# MgdOpna.net
KiCad netlist of a schematic drawn in EAGLE
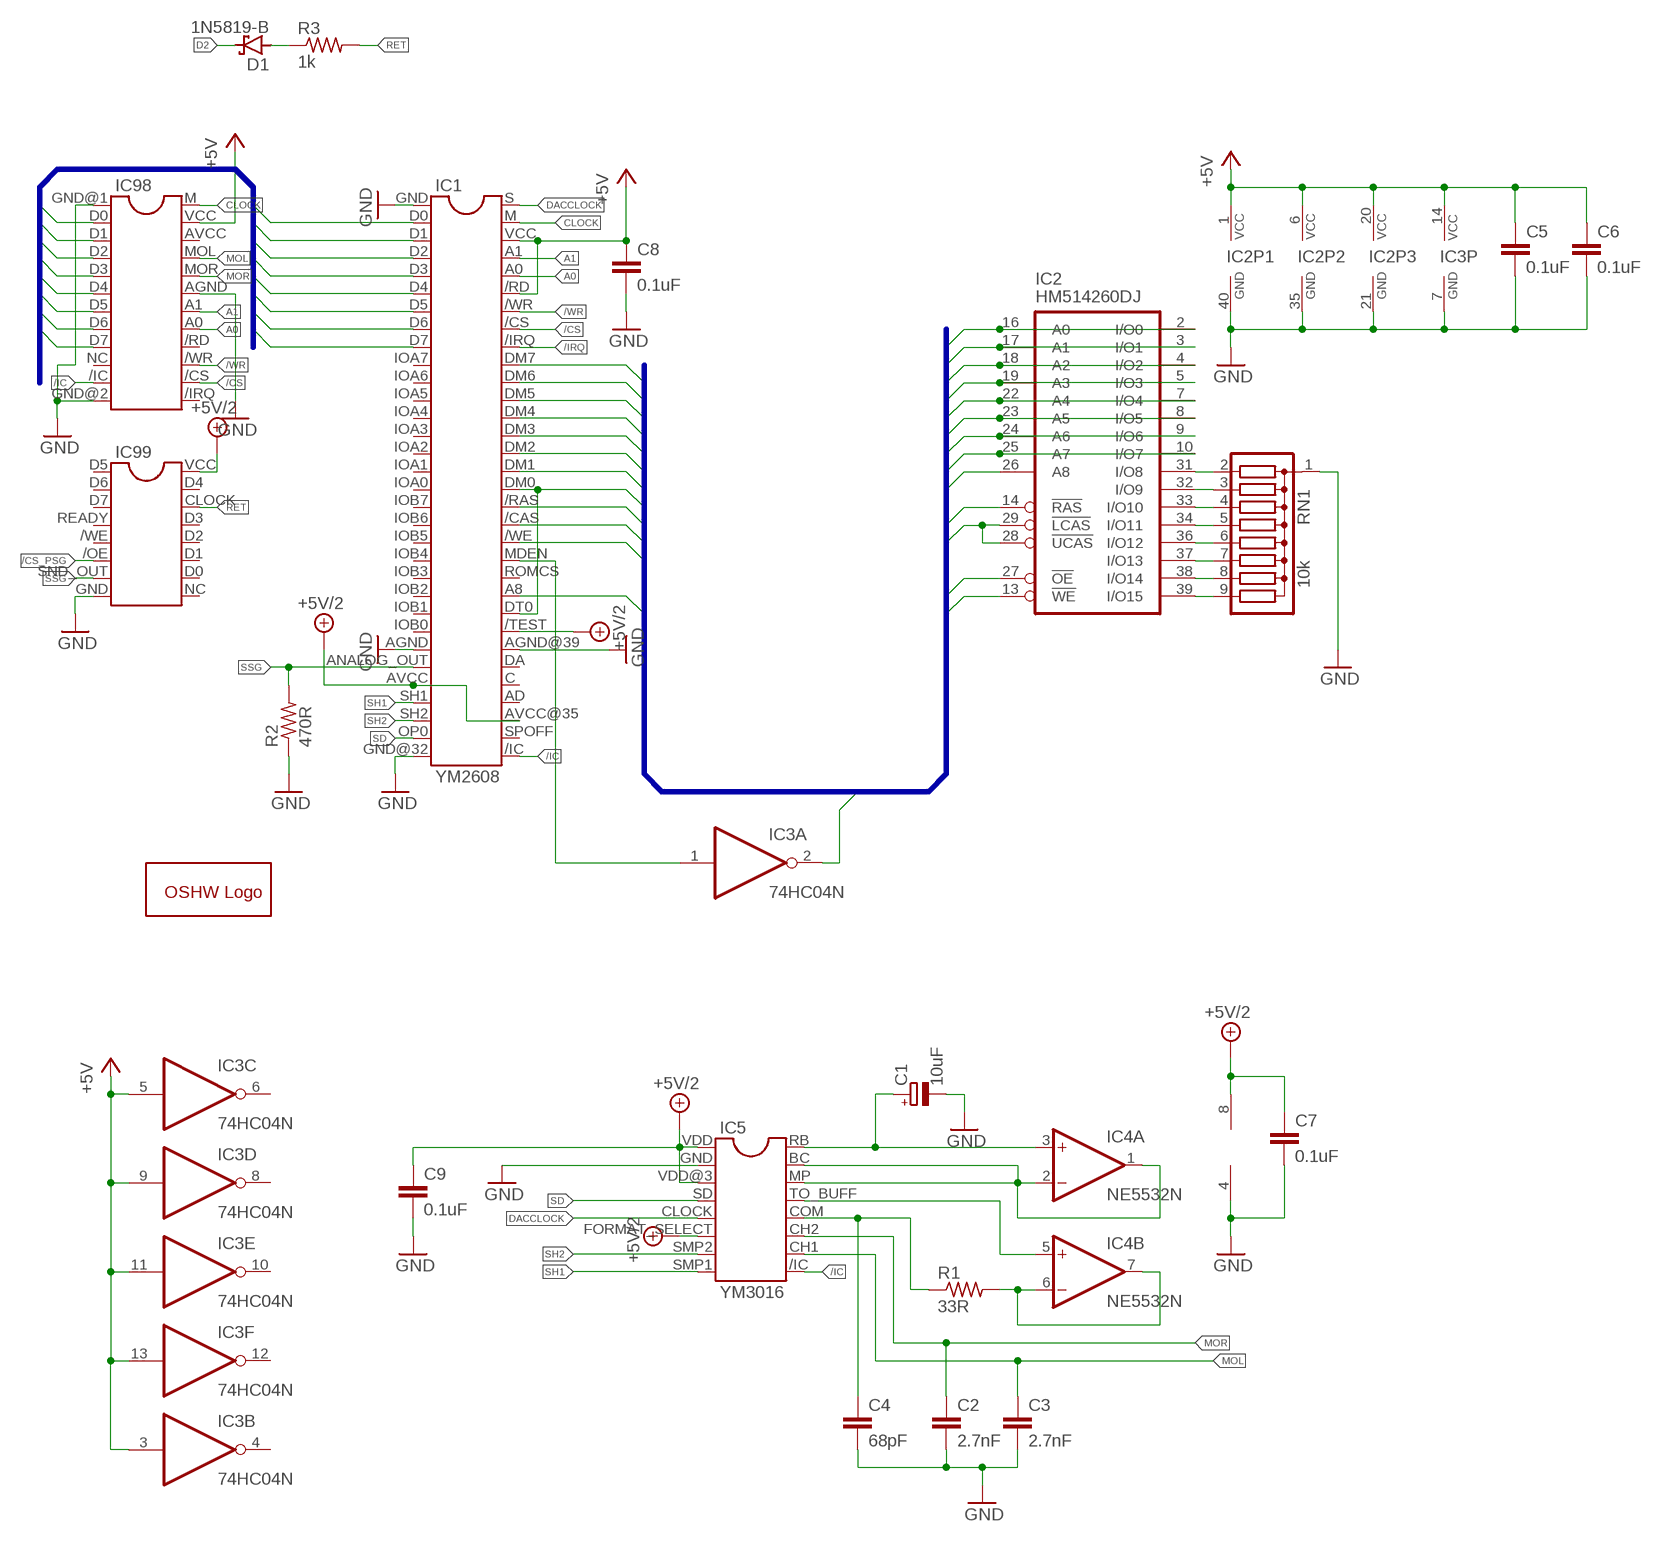
[diagram p0: schematic, sheet 1]

(export (version "E")
  (design (tool "Eeschema 10.0.6"))
  (components
    (comp (ref "C1")
      (value "10uF")
      (footprint "eagle-import:E2,5-5")
      (libsource (lib "eagle-import") (part "CPOL-EUE2.5-5"))
    )
    (comp (ref "C2")
      (value "2.7nF")
      (footprint "eagle-import:C025-024X044")
      (libsource (lib "eagle-import") (part "C-EU025-024X044"))
    )
    (comp (ref "C3")
      (value "2.7nF")
      (footprint "eagle-import:C025-024X044")
      (libsource (lib "eagle-import") (part "C-EU025-024X044"))
    )
    (comp (ref "C4")
      (value "68pF")
      (footprint "eagle-import:C025-024X044")
      (libsource (lib "eagle-import") (part "C-EU025-024X044"))
    )
    (comp (ref "C5")
      (value "0.1uF")
      (footprint "eagle-import:C025-024X044")
      (libsource (lib "eagle-import") (part "C-EU025-024X044"))
    )
    (comp (ref "C6")
      (value "0.1uF")
      (footprint "eagle-import:C025-024X044")
      (libsource (lib "eagle-import") (part "C-EU025-024X044"))
    )
    (comp (ref "C7")
      (value "0.1uF")
      (footprint "eagle-import:C025-024X044")
      (libsource (lib "eagle-import") (part "C-EU025-024X044"))
    )
    (comp (ref "C8")
      (value "0.1uF")
      (footprint "eagle-import:C025-024X044")
      (libsource (lib "eagle-import") (part "C-EU025-024X044"))
    )
    (comp (ref "C9")
      (value "0.1uF")
      (footprint "eagle-import:C025-024X044")
      (libsource (lib "eagle-import") (part "C-EU025-024X044"))
    )
    (comp (ref "D1")
      (value "1N5819-B")
      (footprint "eagle-import:DO41-7.6")
      (libsource (lib "eagle-import") (part "1N5819-B"))
    )
    (comp (ref "GOLD_ORB_SM1")
      (value "OSHWLOGOLOGO8MM")
      (footprint "eagle-import:OSHW_8MM")
      (libsource (lib "eagle-import") (part "OSHWLOGOLOGO8MM"))
    )
    (comp (ref "IC1")
      (value "YM2608")
      (footprint "eagle-import:YM2608")
      (libsource (lib "eagle-import") (part "YM2608"))
    )
    (comp (ref "IC2")
      (value "HM514260DJ")
      (footprint "eagle-import:SOJ40-4")
      (libsource (lib "eagle-import") (part "HM514260DJ"))
    )
    (comp (ref "IC3")
      (value "74HC04N")
      (footprint "eagle-import:DIL14")
      (libsource (lib "eagle-import") (part "7404NHC"))
    )
    (comp (ref "IC4")
      (value "NE5532N")
      (footprint "eagle-import:DIL08")
      (libsource (lib "eagle-import") (part "NE5532N"))
    )
    (comp (ref "IC5")
      (value "YM3016")
      (footprint "eagle-import:YM3016")
      (libsource (lib "eagle-import") (part "YM3016"))
    )
    (comp (ref "IC98")
      (value "YM2612YM2612_NOSILK")
      (footprint "eagle-import:YM2612_NOSILK")
      (libsource (lib "eagle-import") (part "YM2612YM2612_NOSILK"))
    )
    (comp (ref "IC99")
      (value "SN76489SN76489_NOSILK")
      (footprint "eagle-import:SN76489_NOSILK")
      (libsource (lib "eagle-import") (part "SN76489SN76489_NOSILK"))
    )
    (comp (ref "R1")
      (value "33R")
      (footprint "eagle-import:0204_7")
      (libsource (lib "eagle-import") (part "R-US_0204/7"))
    )
    (comp (ref "R2")
      (value "470R")
      (footprint "eagle-import:0204_7")
      (libsource (lib "eagle-import") (part "R-US_0204/7"))
    )
    (comp (ref "R3")
      (value "1k")
      (footprint "eagle-import:0204_7")
      (libsource (lib "eagle-import") (part "R-US_0204/7"))
    )
    (comp (ref "RN1")
      (value "10k")
      (footprint "eagle-import:SIL9")
      (libsource (lib "eagle-import") (part "G08R"))
    )
  )
  (nets
    (net (code "1") (name "+5V") (class "Default")
      (node (ref "C5") (pin "1") (pinfunction "1_1") (pintype "passive"))
      (node (ref "C6") (pin "1") (pinfunction "1_1") (pintype "passive"))
      (node (ref "C8") (pin "1") (pinfunction "1_1") (pintype "passive"))
      (node (ref "IC1") (pin "/RD") (pinfunction "/RD_/RD") (pintype "passive"))
      (node (ref "IC1") (pin "VCC") (pinfunction "VCC_VCC") (pintype "passive"))
      (node (ref "IC2") (pin "1") (pinfunction "VCC_1") (pintype "power_in"))
      (node (ref "IC2") (pin "20") (pinfunction "VCC_20") (pintype "power_in"))
      (node (ref "IC2") (pin "6") (pinfunction "VCC_6") (pintype "power_in"))
      (node (ref "IC3") (pin "11") (pinfunction "I_11") (pintype "input"))
      (node (ref "IC3") (pin "13") (pinfunction "I_13") (pintype "input"))
      (node (ref "IC3") (pin "14") (pinfunction "VCC_14") (pintype "power_in"))
      (node (ref "IC3") (pin "3") (pinfunction "I_3") (pintype "input"))
      (node (ref "IC3") (pin "5") (pinfunction "I_5") (pintype "input"))
      (node (ref "IC3") (pin "9") (pinfunction "I_9") (pintype "input"))
      (node (ref "IC98") (pin "VCC") (pinfunction "VCC_VCC") (pintype "passive"))
    )
    (net (code "2") (name "+5V{slash}2") (class "Default")
      (node (ref "C7") (pin "1") (pinfunction "1_1") (pintype "passive"))
      (node (ref "C9") (pin "1") (pinfunction "1_1") (pintype "passive"))
      (node (ref "IC1") (pin "/TEST") (pinfunction "/TEST_/TEST") (pintype "passive"))
      (node (ref "IC1") (pin "AVCC") (pinfunction "AVCC_AVCC") (pintype "passive"))
      (node (ref "IC1") (pin "AVCC@35") (pinfunction "AVCC_AVCC@35") (pintype "passive"))
      (node (ref "IC4") (pin "8") (pinfunction "V+_8") (pintype "power_in"))
      (node (ref "IC5") (pin "FORMAT_SELECT") (pinfunction "6_FORMAT_SELECT") (pintype "passive"))
      (node (ref "IC5") (pin "VDD") (pinfunction "1_VDD") (pintype "passive"))
      (node (ref "IC5") (pin "VDD@3") (pinfunction "3_VDD@3") (pintype "passive"))
      (node (ref "IC99") (pin "VCC") (pinfunction "VCC_VCC") (pintype "passive"))
    )
    (net (code "3") (name "/A8") (class "Default")
      (node (ref "IC1") (pin "A8") (pinfunction "A8_A8") (pintype "passive"))
      (node (ref "IC2") (pin "26") (pinfunction "A8_26") (pintype "input"))
    )
    (net (code "4") (name "/D0") (class "Default")
      (node (ref "IC1") (pin "D0") (pinfunction "D0_D0") (pintype "passive"))
      (node (ref "IC98") (pin "D0") (pinfunction "D0_D0") (pintype "passive"))
    )
    (net (code "5") (name "/D1") (class "Default")
      (node (ref "IC1") (pin "D1") (pinfunction "D1_D1") (pintype "passive"))
      (node (ref "IC98") (pin "D1") (pinfunction "D1_D1") (pintype "passive"))
    )
    (net (code "6") (name "/D3") (class "Default")
      (node (ref "IC1") (pin "D3") (pinfunction "D3_D3") (pintype "passive"))
      (node (ref "IC98") (pin "D3") (pinfunction "D3_D3") (pintype "passive"))
    )
    (net (code "7") (name "/D4") (class "Default")
      (node (ref "IC1") (pin "D4") (pinfunction "D4_D4") (pintype "passive"))
      (node (ref "IC98") (pin "D4") (pinfunction "D4_D4") (pintype "passive"))
    )
    (net (code "8") (name "/D5") (class "Default")
      (node (ref "IC1") (pin "D5") (pinfunction "D5_D5") (pintype "passive"))
      (node (ref "IC98") (pin "D5") (pinfunction "D5_D5") (pintype "passive"))
    )
    (net (code "9") (name "/D6") (class "Default")
      (node (ref "IC1") (pin "D6") (pinfunction "D6_D6") (pintype "passive"))
      (node (ref "IC98") (pin "D6") (pinfunction "D6_D6") (pintype "passive"))
    )
    (net (code "10") (name "/D7") (class "Default")
      (node (ref "IC1") (pin "D7") (pinfunction "D7_D7") (pintype "passive"))
      (node (ref "IC98") (pin "D7") (pinfunction "D7_D7") (pintype "passive"))
    )
    (net (code "11") (name "/DM0") (class "Default")
      (node (ref "IC1") (pin "DM0") (pinfunction "DM0_DM0") (pintype "passive"))
      (node (ref "IC1") (pin "DT0") (pinfunction "DTO_DT0") (pintype "passive"))
      (node (ref "IC2") (pin "16") (pinfunction "A0_16") (pintype "input"))
      (node (ref "IC2") (pin "2") (pinfunction "I/O0_2") (pintype "tri_state"))
    )
    (net (code "12") (name "/DM1") (class "Default")
      (node (ref "IC1") (pin "DM1") (pinfunction "DM1_DM1") (pintype "passive"))
      (node (ref "IC2") (pin "17") (pinfunction "A1_17") (pintype "input"))
      (node (ref "IC2") (pin "3") (pinfunction "I/O1_3") (pintype "tri_state"))
    )
    (net (code "13") (name "/DM2") (class "Default")
      (node (ref "IC1") (pin "DM2") (pinfunction "DM2_DM2") (pintype "passive"))
      (node (ref "IC2") (pin "18") (pinfunction "A2_18") (pintype "input"))
      (node (ref "IC2") (pin "4") (pinfunction "I/O2_4") (pintype "tri_state"))
    )
    (net (code "14") (name "/DM3") (class "Default")
      (node (ref "IC1") (pin "DM3") (pinfunction "DM3_DM3") (pintype "passive"))
      (node (ref "IC2") (pin "19") (pinfunction "A3_19") (pintype "input"))
      (node (ref "IC2") (pin "5") (pinfunction "I/O3_5") (pintype "tri_state"))
    )
    (net (code "15") (name "/DM4") (class "Default")
      (node (ref "IC1") (pin "DM4") (pinfunction "DM4_DM4") (pintype "passive"))
      (node (ref "IC2") (pin "22") (pinfunction "A4_22") (pintype "input"))
      (node (ref "IC2") (pin "7") (pinfunction "I/O4_7") (pintype "tri_state"))
    )
    (net (code "16") (name "/DM5") (class "Default")
      (node (ref "IC1") (pin "DM5") (pinfunction "DM5_DM5") (pintype "passive"))
      (node (ref "IC2") (pin "23") (pinfunction "A5_23") (pintype "input"))
      (node (ref "IC2") (pin "8") (pinfunction "I/O5_8") (pintype "tri_state"))
    )
    (net (code "17") (name "/DM6") (class "Default")
      (node (ref "IC1") (pin "DM6") (pinfunction "DM6_DM6") (pintype "passive"))
      (node (ref "IC2") (pin "24") (pinfunction "A6_24") (pintype "input"))
      (node (ref "IC2") (pin "9") (pinfunction "I/O6_9") (pintype "tri_state"))
    )
    (net (code "18") (name "/DM7") (class "Default")
      (node (ref "IC1") (pin "DM7") (pinfunction "DM7_DM7") (pintype "passive"))
      (node (ref "IC2") (pin "10") (pinfunction "I/O7_10") (pintype "tri_state"))
      (node (ref "IC2") (pin "25") (pinfunction "A7_25") (pintype "input"))
    )
    (net (code "19") (name "/{slash}CAS") (class "Default")
      (node (ref "IC1") (pin "/CAS") (pinfunction "/CAS_/CAS") (pintype "passive"))
      (node (ref "IC2") (pin "28") (pinfunction "~{UCAS}_28") (pintype "input"))
      (node (ref "IC2") (pin "29") (pinfunction "~{LCAS}_29") (pintype "input"))
    )
    (net (code "20") (name "/{slash}OE") (class "Default")
      (node (ref "IC2") (pin "27") (pinfunction "~{OE}_27") (pintype "input"))
      (node (ref "IC3") (pin "2") (pinfunction "O_2") (pintype "output"))
    )
    (net (code "21") (name "/{slash}RAS") (class "Default")
      (node (ref "IC1") (pin "/RAS") (pinfunction "/RAS_/RAS") (pintype "passive"))
      (node (ref "IC2") (pin "14") (pinfunction "~{RAS}_14") (pintype "input"))
    )
    (net (code "22") (name "/{slash}WE") (class "Default")
      (node (ref "IC1") (pin "/WE") (pinfunction "/WE_/WE") (pintype "passive"))
      (node (ref "IC2") (pin "13") (pinfunction "~{WE}_13") (pintype "input"))
    )
    (net (code "23") (name "A0") (class "Default")
      (node (ref "IC1") (pin "A0") (pinfunction "A0_A0") (pintype "passive"))
      (node (ref "IC98") (pin "A0") (pinfunction "A0_A0") (pintype "passive"))
    )
    (net (code "24") (name "A1") (class "Default")
      (node (ref "IC1") (pin "A1") (pinfunction "A1_A1") (pintype "passive"))
      (node (ref "IC98") (pin "A1") (pinfunction "A1_A1") (pintype "passive"))
    )
    (net (code "25") (name "CLOCK") (class "Default")
      (node (ref "IC1") (pin "M") (pinfunction "M_M") (pintype "passive"))
      (node (ref "IC98") (pin "M") (pinfunction "M_M") (pintype "passive"))
    )
    (net (code "26") (name "D2") (class "Default")
      (node (ref "D1") (pin "C") (pinfunction "C_C") (pintype "passive"))
      (node (ref "IC1") (pin "D2") (pinfunction "D2_D2") (pintype "passive"))
      (node (ref "IC98") (pin "D2") (pinfunction "D2_D2") (pintype "passive"))
    )
    (net (code "27") (name "DACCLOCK") (class "Default")
      (node (ref "IC1") (pin "S") (pinfunction "S_S") (pintype "passive"))
      (node (ref "IC5") (pin "CLOCK") (pinfunction "5_CLOCK") (pintype "passive"))
    )
    (net (code "28") (name "GND") (class "Default")
      (node (ref "C1") (pin "-") (pinfunction "-_-") (pintype "passive"))
      (node (ref "C2") (pin "2") (pinfunction "2_2") (pintype "passive"))
      (node (ref "C3") (pin "2") (pinfunction "2_2") (pintype "passive"))
      (node (ref "C4") (pin "2") (pinfunction "2_2") (pintype "passive"))
      (node (ref "C5") (pin "2") (pinfunction "2_2") (pintype "passive"))
      (node (ref "C6") (pin "2") (pinfunction "2_2") (pintype "passive"))
      (node (ref "C7") (pin "2") (pinfunction "2_2") (pintype "passive"))
      (node (ref "C8") (pin "2") (pinfunction "2_2") (pintype "passive"))
      (node (ref "C9") (pin "2") (pinfunction "2_2") (pintype "passive"))
      (node (ref "IC1") (pin "AGND") (pinfunction "AGND_AGND") (pintype "passive"))
      (node (ref "IC1") (pin "AGND@39") (pinfunction "AGND_AGND@39") (pintype "passive"))
      (node (ref "IC1") (pin "GND") (pinfunction "GND_GND") (pintype "passive"))
      (node (ref "IC1") (pin "GND@32") (pinfunction "GND_GND@32") (pintype "passive"))
      (node (ref "IC2") (pin "21") (pinfunction "GND_21") (pintype "power_in"))
      (node (ref "IC2") (pin "35") (pinfunction "GND_35") (pintype "power_in"))
      (node (ref "IC2") (pin "40") (pinfunction "GND_40") (pintype "power_in"))
      (node (ref "IC3") (pin "7") (pinfunction "GND_7") (pintype "power_in"))
      (node (ref "IC4") (pin "4") (pinfunction "V-_4") (pintype "power_in"))
      (node (ref "IC5") (pin "GND") (pinfunction "2_GND") (pintype "passive"))
      (node (ref "IC98") (pin "AGND") (pinfunction "AGND_AGND") (pintype "passive"))
      (node (ref "IC98") (pin "GND@1") (pinfunction "GND_GND@1") (pintype "passive"))
      (node (ref "IC98") (pin "GND@2") (pinfunction "GND_GND@2") (pintype "passive"))
      (node (ref "IC99") (pin "GND") (pinfunction "GND_GND") (pintype "passive"))
      (node (ref "R2") (pin "1") (pinfunction "1_1") (pintype "passive"))
      (node (ref "RN1") (pin "1") (pinfunction "1_1") (pintype "passive"))
    )
    (net (code "29") (name "MOL") (class "Default")
      (node (ref "C3") (pin "1") (pinfunction "1_1") (pintype "passive"))
      (node (ref "IC5") (pin "CH1") (pinfunction "10_CH1") (pintype "passive"))
      (node (ref "IC98") (pin "MOL") (pinfunction "MOL_MOL") (pintype "passive"))
    )
    (net (code "30") (name "MOR") (class "Default")
      (node (ref "C2") (pin "1") (pinfunction "1_1") (pintype "passive"))
      (node (ref "IC5") (pin "CH2") (pinfunction "11_CH2") (pintype "passive"))
      (node (ref "IC98") (pin "MOR") (pinfunction "MOR_MOR") (pintype "passive"))
    )
    (net (code "31") (name "Net-(D1-PadA)") (class "Default")
      (node (ref "D1") (pin "A") (pinfunction "A_A") (pintype "passive"))
      (node (ref "R3") (pin "1") (pinfunction "1_1") (pintype "passive"))
    )
    (net (code "32") (name "Net-(IC2A-I{slash}O8)") (class "Default")
      (node (ref "IC2") (pin "31") (pinfunction "I/O8_31") (pintype "tri_state"))
      (node (ref "RN1") (pin "2") (pinfunction "2_2") (pintype "passive"))
    )
    (net (code "33") (name "Net-(IC2A-I{slash}O9)") (class "Default")
      (node (ref "IC2") (pin "32") (pinfunction "I/O9_32") (pintype "tri_state"))
      (node (ref "RN1") (pin "3") (pinfunction "3_3") (pintype "passive"))
    )
    (net (code "34") (name "Net-(IC2A-I{slash}O10)") (class "Default")
      (node (ref "IC2") (pin "33") (pinfunction "I/O10_33") (pintype "tri_state"))
      (node (ref "RN1") (pin "4") (pinfunction "4_4") (pintype "passive"))
    )
    (net (code "35") (name "Net-(IC2A-I{slash}O11)") (class "Default")
      (node (ref "IC2") (pin "34") (pinfunction "I/O11_34") (pintype "tri_state"))
      (node (ref "RN1") (pin "5") (pinfunction "5_5") (pintype "passive"))
    )
    (net (code "36") (name "Net-(IC2A-I{slash}O12)") (class "Default")
      (node (ref "IC2") (pin "36") (pinfunction "I/O12_36") (pintype "tri_state"))
      (node (ref "RN1") (pin "6") (pinfunction "6_6") (pintype "passive"))
    )
    (net (code "37") (name "Net-(IC2A-I{slash}O13)") (class "Default")
      (node (ref "IC2") (pin "37") (pinfunction "I/O13_37") (pintype "tri_state"))
      (node (ref "RN1") (pin "7") (pinfunction "7_7") (pintype "passive"))
    )
    (net (code "38") (name "Net-(IC2A-I{slash}O14)") (class "Default")
      (node (ref "IC2") (pin "38") (pinfunction "I/O14_38") (pintype "tri_state"))
      (node (ref "RN1") (pin "8") (pinfunction "8_8") (pintype "passive"))
    )
    (net (code "39") (name "Net-(IC2A-I{slash}O15)") (class "Default")
      (node (ref "IC2") (pin "39") (pinfunction "I/O15_39") (pintype "tri_state"))
      (node (ref "RN1") (pin "9") (pinfunction "9_9") (pintype "passive"))
    )
    (net (code "40") (name "Net-(IC3A-I)") (class "Default")
      (node (ref "IC1") (pin "MDEN") (pinfunction "MDEN_MDEN") (pintype "passive"))
      (node (ref "IC3") (pin "1") (pinfunction "I_1") (pintype "input"))
    )
    (net (code "41") (name "Net-(IC4A-+IN)") (class "Default")
      (node (ref "C1") (pin "+") (pinfunction "+_+") (pintype "passive"))
      (node (ref "IC4") (pin "3") (pinfunction "+IN_3") (pintype "input"))
      (node (ref "IC5") (pin "RB") (pinfunction "16_RB") (pintype "passive"))
    )
    (net (code "42") (name "Net-(IC4A--IN)") (class "Default")
      (node (ref "IC4") (pin "1") (pinfunction "OUT_1") (pintype "output"))
      (node (ref "IC4") (pin "2") (pinfunction "-IN_2") (pintype "input"))
      (node (ref "IC5") (pin "BC") (pinfunction "15_BC") (pintype "passive"))
      (node (ref "IC5") (pin "MP") (pinfunction "14_MP") (pintype "passive"))
    )
    (net (code "43") (name "Net-(IC4B-+IN)") (class "Default")
      (node (ref "IC4") (pin "5") (pinfunction "+IN_5") (pintype "input"))
      (node (ref "IC5") (pin "TO_BUFF") (pinfunction "13_TO_BUFF") (pintype "passive"))
    )
    (net (code "44") (name "Net-(IC4B--IN)") (class "Default")
      (node (ref "IC4") (pin "6") (pinfunction "-IN_6") (pintype "input"))
      (node (ref "IC4") (pin "7") (pinfunction "OUT_7") (pintype "output"))
      (node (ref "R1") (pin "2") (pinfunction "2_2") (pintype "passive"))
    )
    (net (code "45") (name "Net-(IC5-12)") (class "Default")
      (node (ref "C4") (pin "1") (pinfunction "1_1") (pintype "passive"))
      (node (ref "IC5") (pin "COM") (pinfunction "12_COM") (pintype "passive"))
      (node (ref "R1") (pin "1") (pinfunction "1_1") (pintype "passive"))
    )
    (net (code "46") (name "RET") (class "Default")
      (node (ref "IC99") (pin "CLOCK") (pinfunction "CLOCK_CLOCK") (pintype "passive"))
      (node (ref "R3") (pin "2") (pinfunction "2_2") (pintype "passive"))
    )
    (net (code "47") (name "SD") (class "Default")
      (node (ref "IC1") (pin "OP0") (pinfunction "OP0_OP0") (pintype "passive"))
      (node (ref "IC5") (pin "SD") (pinfunction "4_SD") (pintype "passive"))
    )
    (net (code "48") (name "SH1") (class "Default")
      (node (ref "IC1") (pin "SH1") (pinfunction "SH1_SH1") (pintype "passive"))
      (node (ref "IC5") (pin "SMP1") (pinfunction "8_SMP1") (pintype "passive"))
    )
    (net (code "49") (name "SH2") (class "Default")
      (node (ref "IC1") (pin "SH2") (pinfunction "SH2_SH2") (pintype "passive"))
      (node (ref "IC5") (pin "SMP2") (pinfunction "7_SMP2") (pintype "passive"))
    )
    (net (code "50") (name "SSG") (class "Default")
      (node (ref "IC1") (pin "ANALOG_OUT") (pinfunction "ANALOG_OUT_ANALOG_OUT") (pintype "passive"))
      (node (ref "IC99") (pin "SND_OUT") (pinfunction "SND_OUT_SND_OUT") (pintype "passive"))
      (node (ref "R2") (pin "2") (pinfunction "2_2") (pintype "passive"))
    )
    (net (code "51") (name "unconnected-(IC1-PadAD)") (class "Default")
      (node (ref "IC1") (pin "AD") (pinfunction "AD_AD") (pintype "passive"))
    )
    (net (code "52") (name "unconnected-(IC1-PadC)") (class "Default")
      (node (ref "IC1") (pin "C") (pinfunction "C_C") (pintype "passive"))
    )
    (net (code "53") (name "unconnected-(IC1-PadDA)") (class "Default")
      (node (ref "IC1") (pin "DA") (pinfunction "DA_DA") (pintype "passive"))
    )
    (net (code "54") (name "unconnected-(IC1-PadIOA0)") (class "Default")
      (node (ref "IC1") (pin "IOA0") (pinfunction "IOA0_IOA0") (pintype "passive"))
    )
    (net (code "55") (name "unconnected-(IC1-PadIOA1)") (class "Default")
      (node (ref "IC1") (pin "IOA1") (pinfunction "IOA1_IOA1") (pintype "passive"))
    )
    (net (code "56") (name "unconnected-(IC1-PadIOA2)") (class "Default")
      (node (ref "IC1") (pin "IOA2") (pinfunction "IOA2_IOA2") (pintype "passive"))
    )
    (net (code "57") (name "unconnected-(IC1-PadIOA3)") (class "Default")
      (node (ref "IC1") (pin "IOA3") (pinfunction "IOA3_IOA3") (pintype "passive"))
    )
    (net (code "58") (name "unconnected-(IC1-PadIOA4)") (class "Default")
      (node (ref "IC1") (pin "IOA4") (pinfunction "IOA4_IOA4") (pintype "passive"))
    )
    (net (code "59") (name "unconnected-(IC1-PadIOA5)") (class "Default")
      (node (ref "IC1") (pin "IOA5") (pinfunction "IOA5_IOA5") (pintype "passive"))
    )
    (net (code "60") (name "unconnected-(IC1-PadIOA6)") (class "Default")
      (node (ref "IC1") (pin "IOA6") (pinfunction "IOA6_IOA6") (pintype "passive"))
    )
    (net (code "61") (name "unconnected-(IC1-PadIOA7)") (class "Default")
      (node (ref "IC1") (pin "IOA7") (pinfunction "IOA7_IOA7") (pintype "passive"))
    )
    (net (code "62") (name "unconnected-(IC1-PadIOB0)") (class "Default")
      (node (ref "IC1") (pin "IOB0") (pinfunction "IOB0_IOB0") (pintype "passive"))
    )
    (net (code "63") (name "unconnected-(IC1-PadIOB1)") (class "Default")
      (node (ref "IC1") (pin "IOB1") (pinfunction "IOB1_IOB1") (pintype "passive"))
    )
    (net (code "64") (name "unconnected-(IC1-PadIOB2)") (class "Default")
      (node (ref "IC1") (pin "IOB2") (pinfunction "IOB2_IOB2") (pintype "passive"))
    )
    (net (code "65") (name "unconnected-(IC1-PadIOB3)") (class "Default")
      (node (ref "IC1") (pin "IOB3") (pinfunction "IOB3_IOB3") (pintype "passive"))
    )
    (net (code "66") (name "unconnected-(IC1-PadIOB4)") (class "Default")
      (node (ref "IC1") (pin "IOB4") (pinfunction "IOB4_IOB4") (pintype "passive"))
    )
    (net (code "67") (name "unconnected-(IC1-PadIOB5)") (class "Default")
      (node (ref "IC1") (pin "IOB5") (pinfunction "IOB5_IOB5") (pintype "passive"))
    )
    (net (code "68") (name "unconnected-(IC1-PadIOB6)") (class "Default")
      (node (ref "IC1") (pin "IOB6") (pinfunction "IOB6_IOB6") (pintype "passive"))
    )
    (net (code "69") (name "unconnected-(IC1-PadIOB7)") (class "Default")
      (node (ref "IC1") (pin "IOB7") (pinfunction "IOB7_IOB7") (pintype "passive"))
    )
    (net (code "70") (name "unconnected-(IC1-PadROMCS)") (class "Default")
      (node (ref "IC1") (pin "ROMCS") (pinfunction "ROMCS_ROMCS") (pintype "passive"))
    )
    (net (code "71") (name "unconnected-(IC1-PadSPOFF)") (class "Default")
      (node (ref "IC1") (pin "SPOFF") (pinfunction "SPOFF_SPOFF") (pintype "passive"))
    )
    (net (code "72") (name "unconnected-(IC3B-O-Pad4)") (class "Default")
      (node (ref "IC3") (pin "4") (pinfunction "O_4") (pintype "output"))
    )
    (net (code "73") (name "unconnected-(IC3C-O-Pad6)") (class "Default")
      (node (ref "IC3") (pin "6") (pinfunction "O_6") (pintype "output"))
    )
    (net (code "74") (name "unconnected-(IC3D-O-Pad8)") (class "Default")
      (node (ref "IC3") (pin "8") (pinfunction "O_8") (pintype "output"))
    )
    (net (code "75") (name "unconnected-(IC3E-O-Pad10)") (class "Default")
      (node (ref "IC3") (pin "10") (pinfunction "O_10") (pintype "output"))
    )
    (net (code "76") (name "unconnected-(IC3F-O-Pad12)") (class "Default")
      (node (ref "IC3") (pin "12") (pinfunction "O_12") (pintype "output"))
    )
    (net (code "77") (name "unconnected-(IC98-PadAVCC)") (class "Default")
      (node (ref "IC98") (pin "AVCC") (pinfunction "AVCC_AVCC") (pintype "passive"))
    )
    (net (code "78") (name "unconnected-(IC98-PadNC)") (class "Default")
      (node (ref "IC98") (pin "NC") (pinfunction "NC_NC") (pintype "passive"))
    )
    (net (code "79") (name "unconnected-(IC98-Pad{slash}IRQ)") (class "Default")
      (node (ref "IC98") (pin "/IRQ") (pinfunction "/IRQ_/IRQ") (pintype "passive"))
    )
    (net (code "80") (name "unconnected-(IC98-Pad{slash}RD)") (class "Default")
      (node (ref "IC98") (pin "/RD") (pinfunction "/RD_/RD") (pintype "passive"))
    )
    (net (code "81") (name "unconnected-(IC99-PadD0)") (class "Default")
      (node (ref "IC99") (pin "D0") (pinfunction "D0_D0") (pintype "passive"))
    )
    (net (code "82") (name "unconnected-(IC99-PadD1)") (class "Default")
      (node (ref "IC99") (pin "D1") (pinfunction "D1_D1") (pintype "passive"))
    )
    (net (code "83") (name "unconnected-(IC99-PadD2)") (class "Default")
      (node (ref "IC99") (pin "D2") (pinfunction "D2_D2") (pintype "passive"))
    )
    (net (code "84") (name "unconnected-(IC99-PadD3)") (class "Default")
      (node (ref "IC99") (pin "D3") (pinfunction "D3_D3") (pintype "passive"))
    )
    (net (code "85") (name "unconnected-(IC99-PadD4)") (class "Default")
      (node (ref "IC99") (pin "D4") (pinfunction "D4_D4") (pintype "passive"))
    )
    (net (code "86") (name "unconnected-(IC99-PadD5)") (class "Default")
      (node (ref "IC99") (pin "D5") (pinfunction "D5_D5") (pintype "passive"))
    )
    (net (code "87") (name "unconnected-(IC99-PadD6)") (class "Default")
      (node (ref "IC99") (pin "D6") (pinfunction "D6_D6") (pintype "passive"))
    )
    (net (code "88") (name "unconnected-(IC99-PadD7)") (class "Default")
      (node (ref "IC99") (pin "D7") (pinfunction "D7_D7") (pintype "passive"))
    )
    (net (code "89") (name "unconnected-(IC99-PadNC)") (class "Default")
      (node (ref "IC99") (pin "NC") (pinfunction "NC_NC") (pintype "passive"))
    )
    (net (code "90") (name "unconnected-(IC99-PadREADY)") (class "Default")
      (node (ref "IC99") (pin "READY") (pinfunction "READY_READY") (pintype "passive"))
    )
    (net (code "91") (name "unconnected-(IC99-Pad{slash}WE)") (class "Default")
      (node (ref "IC99") (pin "/WE") (pinfunction "/WE_/WE") (pintype "passive"))
    )
    (net (code "92") (name "{slash}CS") (class "Default")
      (node (ref "IC1") (pin "/CS") (pinfunction "/CS_/CS") (pintype "passive"))
      (node (ref "IC98") (pin "/CS") (pinfunction "/CS_/CS") (pintype "passive"))
    )
    (net (code "93") (name "{slash}CS_PSG") (class "Default")
      (node (ref "IC99") (pin "/OE") (pinfunction "/OE_/OE") (pintype "passive"))
    )
    (net (code "94") (name "{slash}IC") (class "Default")
      (node (ref "IC1") (pin "/IC") (pinfunction "/IC_/IC") (pintype "passive"))
      (node (ref "IC5") (pin "/IC") (pinfunction "9_/IC") (pintype "passive"))
      (node (ref "IC98") (pin "/IC") (pinfunction "/IC_/IC") (pintype "passive"))
    )
    (net (code "95") (name "{slash}IRQ") (class "Default")
      (node (ref "IC1") (pin "/IRQ") (pinfunction "/IRQ_/IRQ") (pintype "passive"))
    )
    (net (code "96") (name "{slash}WR") (class "Default")
      (node (ref "IC1") (pin "/WR") (pinfunction "/WR_/WR") (pintype "passive"))
      (node (ref "IC98") (pin "/WR") (pinfunction "/WR_/WR") (pintype "passive"))
    )
  )
)
